# BMS_Design_2_New_Part_Monitor.net
KiCad netlist of a schematic drawn in Altium Designer
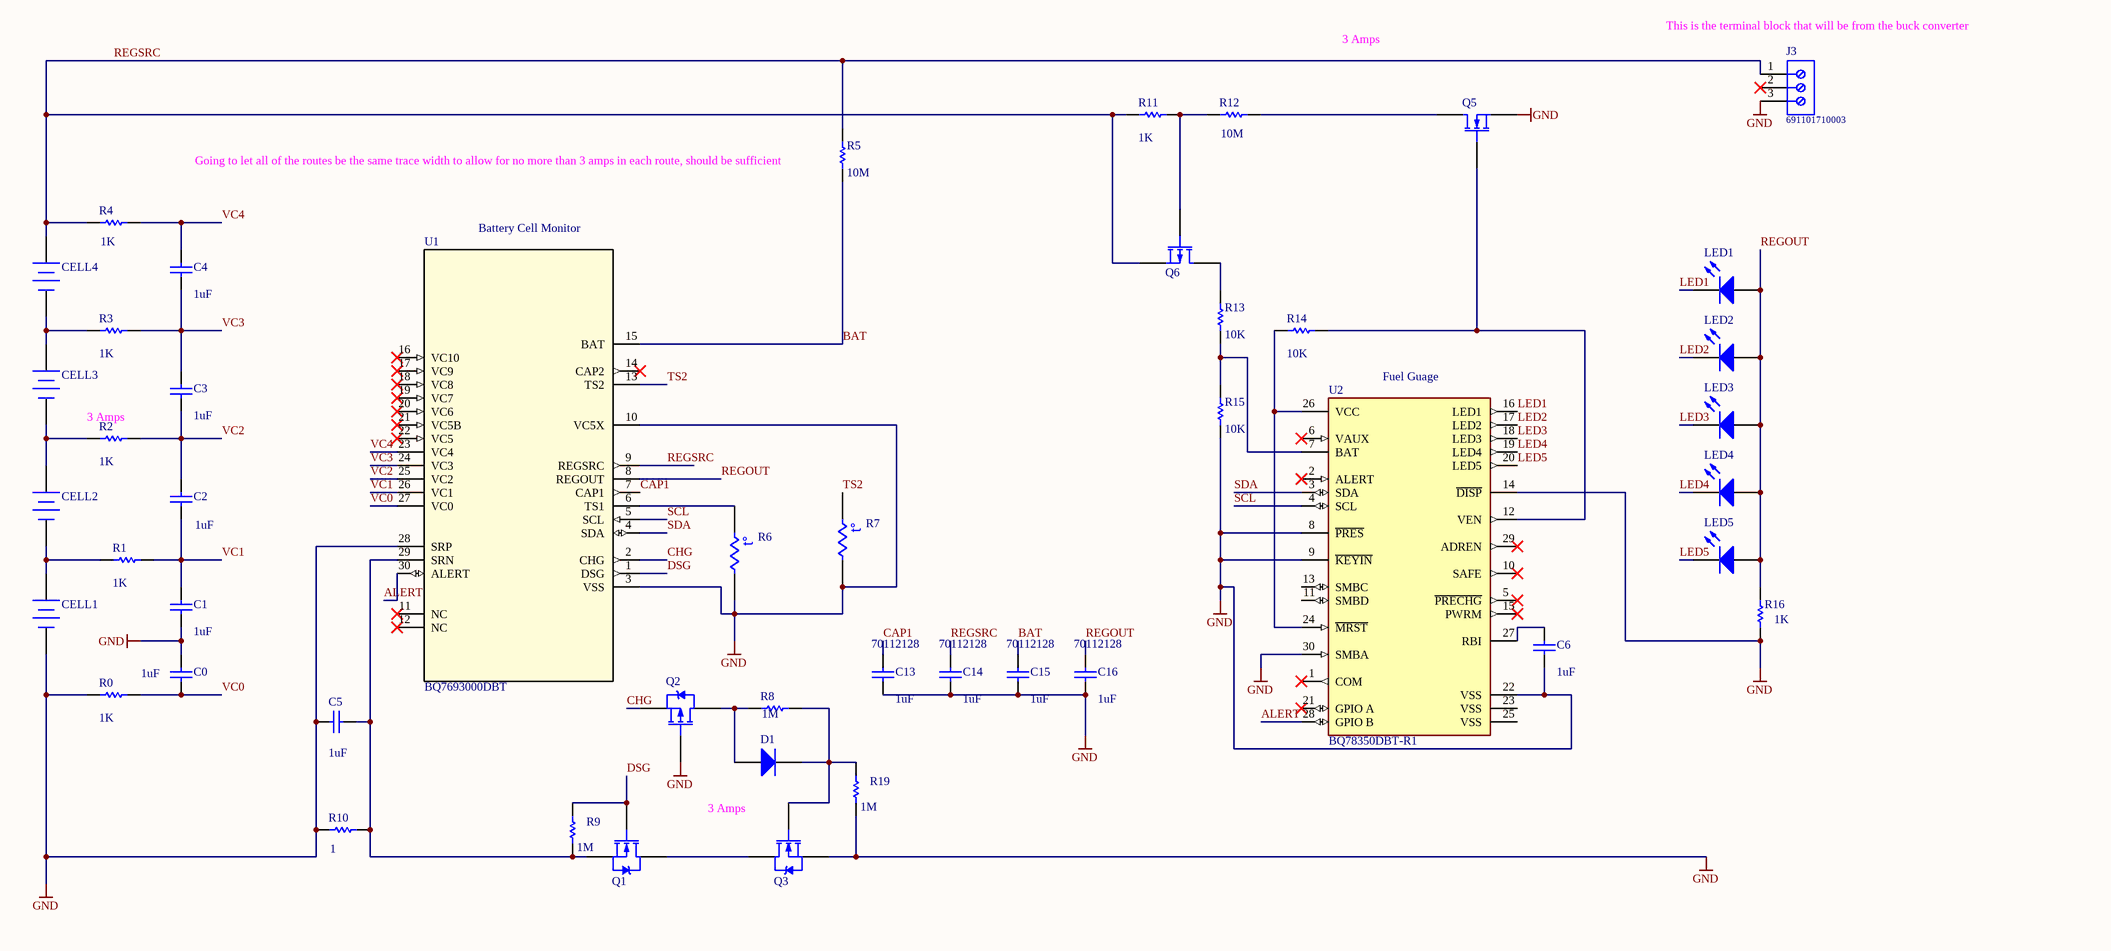
[diagram p0: BMS Design 2 New Part Monitor.SchDoc]

(export (version "E")
  (design (tool "Eeschema 10.0.6"))
  (components
    (comp (ref "C0")
      (value "1uF")
      (footprint "RAD-0.3")
      (description "Capacitor")
      (fields (field (name "PUBLISHER") "Altium Limited"))
      (libsource (lib "Miscellaneous Devices") (part "Cap"))
    )
    (comp (ref "C1")
      (value "1uF")
      (footprint "RAD-0.3")
      (description "Capacitor")
      (fields (field (name "PUBLISHER") "Altium Limited"))
      (libsource (lib "Miscellaneous Devices") (part "Cap"))
    )
    (comp (ref "C2")
      (value "1uF")
      (footprint "RAD-0.3")
      (description "Capacitor")
      (fields (field (name "PUBLISHER") "Altium Limited"))
      (libsource (lib "Miscellaneous Devices") (part "Cap"))
    )
    (comp (ref "C3")
      (value "1uF")
      (footprint "RAD-0.3")
      (description "Capacitor")
      (fields (field (name "PUBLISHER") "Altium Limited"))
      (libsource (lib "Miscellaneous Devices") (part "Cap"))
    )
    (comp (ref "C4")
      (value "1uF")
      (footprint "RAD-0.3")
      (description "Capacitor")
      (fields (field (name "PUBLISHER") "Altium Limited"))
      (libsource (lib "Miscellaneous Devices") (part "Cap"))
    )
    (comp (ref "C5")
      (value "1uF")
      (footprint "RAD-0.3")
      (description "Capacitor")
      (fields (field (name "PUBLISHER") "Altium Limited"))
      (libsource (lib "Miscellaneous Devices") (part "Cap"))
    )
    (comp (ref "C6")
      (value "1uF")
      (footprint "RAD-0.3")
      (description "Capacitor")
      (fields (field (name "PUBLISHER") "Altium Limited"))
      (libsource (lib "Miscellaneous Devices") (part "Cap"))
    )
    (comp (ref "C13")
      (value "1uF")
      (footprint "RAD-0.3")
      (description "Capacitor")
      (fields (field (name "SUPPLIER PART NUMBER 1") "70112128") (field (name "PUBLISHER") "Altium Limited"))
      (libsource (lib "Miscellaneous Devices") (part "Cap"))
    )
    (comp (ref "C14")
      (value "1uF")
      (footprint "RAD-0.3")
      (description "Capacitor")
      (fields (field (name "SUPPLIER PART NUMBER 1") "70112128") (field (name "PUBLISHER") "Altium Limited"))
      (libsource (lib "Miscellaneous Devices") (part "Cap"))
    )
    (comp (ref "C15")
      (value "1uF")
      (footprint "RAD-0.3")
      (description "Capacitor")
      (fields (field (name "SUPPLIER PART NUMBER 1") "70112128") (field (name "PUBLISHER") "Altium Limited"))
      (libsource (lib "Miscellaneous Devices") (part "Cap"))
    )
    (comp (ref "C16")
      (value "1uF")
      (footprint "RAD-0.3")
      (description "Capacitor")
      (fields (field (name "SUPPLIER PART NUMBER 1") "70112128") (field (name "PUBLISHER") "Altium Limited"))
      (libsource (lib "Miscellaneous Devices") (part "Cap"))
    )
    (comp (ref "CELL1")
      (value "~")
      (footprint "BAT-2")
      (description "Multicell Battery")
      (fields (field (name "PUBLISHER") "Altium Limited"))
      (libsource (lib "Miscellaneous Devices") (part "Battery"))
    )
    (comp (ref "CELL2")
      (value "~")
      (footprint "BAT-2")
      (description "Multicell Battery")
      (fields (field (name "PUBLISHER") "Altium Limited"))
      (libsource (lib "Miscellaneous Devices") (part "Battery"))
    )
    (comp (ref "CELL3")
      (value "~")
      (footprint "BAT-2")
      (description "Multicell Battery")
      (fields (field (name "PUBLISHER") "Altium Limited"))
      (libsource (lib "Miscellaneous Devices") (part "Battery"))
    )
    (comp (ref "CELL4")
      (value "~")
      (footprint "BAT-2")
      (description "Multicell Battery")
      (fields (field (name "PUBLISHER") "Altium Limited"))
      (libsource (lib "Miscellaneous Devices") (part "Battery"))
    )
    (comp (ref "D1")
      (value "~")
      (footprint "SMC")
      (description "Default Diode")
      (fields (field (name "PUBLISHER") "Altium Limited"))
      (libsource (lib "Miscellaneous Devices") (part "Diode"))
    )
    (comp (ref "J3")
      (value "691101710003")
      (footprint "691101710003")
      (description "Series 101 - 5.00 mm Horizontal Entry Modular with Pressure Clamp WR-TBL, 3 pin")
      (fields (field (name "MANUFACTURER") "Wurth Elektronik") (field (name "PUBLISHER") "WurthElektronik"))
      (libsource (lib "Altium Content Vault") (part "WE-CN-1P-F-TB3"))
    )
    (comp (ref "LED1")
      (value "~")
      (footprint "LED-0")
      (description "Typical INFRARED GaAs LED")
      (fields (field (name "PUBLISHER") "Altium Limited"))
      (libsource (lib "Miscellaneous Devices") (part "LED0"))
    )
    (comp (ref "LED2")
      (value "~")
      (footprint "LED-0")
      (description "Typical INFRARED GaAs LED")
      (fields (field (name "PUBLISHER") "Altium Limited"))
      (libsource (lib "Miscellaneous Devices") (part "LED0"))
    )
    (comp (ref "LED3")
      (value "~")
      (footprint "LED-0")
      (description "Typical INFRARED GaAs LED")
      (fields (field (name "PUBLISHER") "Altium Limited"))
      (libsource (lib "Miscellaneous Devices") (part "LED0"))
    )
    (comp (ref "LED4")
      (value "~")
      (footprint "LED-0")
      (description "Typical INFRARED GaAs LED")
      (fields (field (name "PUBLISHER") "Altium Limited"))
      (libsource (lib "Miscellaneous Devices") (part "LED0"))
    )
    (comp (ref "LED5")
      (value "~")
      (footprint "LED-0")
      (description "Typical INFRARED GaAs LED")
      (fields (field (name "PUBLISHER") "Altium Limited"))
      (libsource (lib "Miscellaneous Devices") (part "LED0"))
    )
    (comp (ref "Q1")
      (value "~")
      (footprint "TO-220AB")
      (description "N-Channel Power MOSFET")
      (fields (field (name "PUBLISHER") "Altium Limited"))
      (libsource (lib "Miscellaneous Devices") (part "NMOS-2"))
    )
    (comp (ref "Q2")
      (value "~")
      (footprint "TO-220AB")
      (description "P-Channel Power MOSFET")
      (fields (field (name "PUBLISHER") "Altium Limited"))
      (libsource (lib "Miscellaneous Devices") (part "PMOS-2"))
    )
    (comp (ref "Q3")
      (value "~")
      (footprint "TO-220AB")
      (description "N-Channel Power MOSFET")
      (fields (field (name "PUBLISHER") "Altium Limited"))
      (libsource (lib "Miscellaneous Devices") (part "NMOS-2"))
    )
    (comp (ref "Q5")
      (value "~")
      (footprint "E3")
      (description "N-Channel MOSFET")
      (fields (field (name "PUBLISHER") "Altium Limited"))
      (libsource (lib "Miscellaneous Devices") (part "MOSFET-N"))
    )
    (comp (ref "Q6")
      (value "~")
      (footprint "E3")
      (description "P-Channel MOSFET")
      (fields (field (name "PUBLISHER") "Altium Limited"))
      (libsource (lib "Miscellaneous Devices") (part "MOSFET-P"))
    )
    (comp (ref "R0")
      (value "1K")
      (footprint "AXIAL-0.3")
      (description "Resistor")
      (fields (field (name "PUBLISHER") "Altium Limited"))
      (libsource (lib "Miscellaneous Devices") (part "Res1"))
    )
    (comp (ref "R1")
      (value "1K")
      (footprint "AXIAL-0.3")
      (description "Resistor")
      (fields (field (name "PUBLISHER") "Altium Limited"))
      (libsource (lib "Miscellaneous Devices") (part "Res1"))
    )
    (comp (ref "R2")
      (value "1K")
      (footprint "AXIAL-0.3")
      (description "Resistor")
      (fields (field (name "PUBLISHER") "Altium Limited"))
      (libsource (lib "Miscellaneous Devices") (part "Res1"))
    )
    (comp (ref "R3")
      (value "1K")
      (footprint "AXIAL-0.3")
      (description "Resistor")
      (fields (field (name "PUBLISHER") "Altium Limited"))
      (libsource (lib "Miscellaneous Devices") (part "Res1"))
    )
    (comp (ref "R4")
      (value "1K")
      (footprint "AXIAL-0.3")
      (description "Resistor")
      (fields (field (name "PUBLISHER") "Altium Limited"))
      (libsource (lib "Miscellaneous Devices") (part "Res1"))
    )
    (comp (ref "R5")
      (value "10M")
      (footprint "AXIAL-0.3")
      (description "Resistor")
      (fields (field (name "PUBLISHER") "Altium Limited"))
      (libsource (lib "Miscellaneous Devices") (part "Res1"))
    )
    (comp (ref "R6")
      (value "~")
      (footprint "6-0805_N")
      (description "Thermistor")
      (fields (field (name "PUBLISHER") "Altium Limited"))
      (libsource (lib "Miscellaneous Devices") (part "Res Thermal"))
    )
    (comp (ref "R7")
      (value "~")
      (footprint "6-0805_N")
      (description "Thermistor")
      (fields (field (name "PUBLISHER") "Altium Limited"))
      (libsource (lib "Miscellaneous Devices") (part "Res Thermal"))
    )
    (comp (ref "R8")
      (value "1M")
      (footprint "AXIAL-0.3")
      (description "Resistor")
      (fields (field (name "PUBLISHER") "Altium Limited"))
      (libsource (lib "Miscellaneous Devices") (part "Res1"))
    )
    (comp (ref "R9")
      (value "1M")
      (footprint "AXIAL-0.3")
      (description "Resistor")
      (fields (field (name "PUBLISHER") "Altium Limited"))
      (libsource (lib "Miscellaneous Devices") (part "Res1"))
    )
    (comp (ref "R10")
      (value "~")
      (footprint "AXIAL-0.3")
      (description "Resistor")
      (fields (field (name "R10") "1") (field (name "PUBLISHER") "Altium Limited"))
      (libsource (lib "Miscellaneous Devices") (part "Res1"))
    )
    (comp (ref "R11")
      (value "1K")
      (footprint "AXIAL-0.3")
      (description "Resistor")
      (fields (field (name "PUBLISHER") "Altium Limited"))
      (libsource (lib "Miscellaneous Devices") (part "Res1"))
    )
    (comp (ref "R12")
      (value "10M")
      (footprint "AXIAL-0.3")
      (description "Resistor")
      (fields (field (name "PUBLISHER") "Altium Limited"))
      (libsource (lib "Miscellaneous Devices") (part "Res1"))
    )
    (comp (ref "R13")
      (value "10K")
      (footprint "AXIAL-0.3")
      (description "Resistor")
      (fields (field (name "PUBLISHER") "Altium Limited"))
      (libsource (lib "Miscellaneous Devices") (part "Res1"))
    )
    (comp (ref "R14")
      (value "10K")
      (footprint "AXIAL-0.3")
      (description "Resistor")
      (fields (field (name "PUBLISHER") "Altium Limited"))
      (libsource (lib "Miscellaneous Devices") (part "Res1"))
    )
    (comp (ref "R15")
      (value "10K")
      (footprint "AXIAL-0.3")
      (description "Resistor")
      (fields (field (name "PUBLISHER") "Altium Limited"))
      (libsource (lib "Miscellaneous Devices") (part "Res1"))
    )
    (comp (ref "R16")
      (value "1K")
      (footprint "AXIAL-0.3")
      (description "Resistor")
      (fields (field (name "PUBLISHER") "Altium Limited"))
      (libsource (lib "Miscellaneous Devices") (part "Res1"))
    )
    (comp (ref "R19")
      (value "1M")
      (footprint "AXIAL-0.3")
      (description "Resistor")
      (fields (field (name "PUBLISHER") "Altium Limited"))
      (libsource (lib "Miscellaneous Devices") (part "Res1"))
    )
    (comp (ref "U1")
      (value "BQ7693000DBT")
      (footprint "BQ7693000DBT:DBT0030A_N")
      (description "No Description Available")
      (fields (field (name "COPYRIGHT") "Copyright (C) 2022 Ultra Librarian. All rights reserved."))
      (libsource (lib "BQ7693000DBT") (part "BQ7693000DBT"))
    )
    (comp (ref "U2")
      (value "BQ78350DBT-R1")
      (footprint "FP-DBT0030A-IPC_C")
      (description "IC BATTERY MGMT CTRLR 30TSSOP")
      (libsource (lib "Altium Content Vault") (part "ce2f43281ae33b5194046e95201acc2"))
    )
  )
  (nets
    (net (code "1") (name "/ALERT") (class "Default")
      (node (ref "U1") (pin "30") (pinfunction "ALERT_30") (pintype "bidirectional"))
      (node (ref "U2") (pin "28") (pinfunction "GPIO_B_28") (pintype "bidirectional"))
    )
    (net (code "2") (name "/BAT") (class "Default")
      (node (ref "C15") (pin "2") (pinfunction "2_2") (pintype "passive"))
      (node (ref "R5") (pin "1") (pinfunction "1_1") (pintype "passive"))
      (node (ref "U1") (pin "15") (pinfunction "BAT_15") (pintype "power_in"))
    )
    (net (code "3") (name "/CAP1") (class "Default")
      (node (ref "C13") (pin "2") (pinfunction "2_2") (pintype "passive"))
      (node (ref "U1") (pin "7") (pinfunction "CAP1_7") (pintype "output"))
    )
    (net (code "4") (name "/CHG") (class "Default")
      (node (ref "Q2") (pin "3") (pinfunction "S_3") (pintype "passive"))
      (node (ref "U1") (pin "2") (pinfunction "CHG_2") (pintype "output"))
    )
    (net (code "5") (name "/DSG") (class "Default")
      (node (ref "Q1") (pin "1") (pinfunction "G_1") (pintype "passive"))
      (node (ref "R9") (pin "2") (pinfunction "2_2") (pintype "passive"))
      (node (ref "U1") (pin "1") (pinfunction "DSG_1") (pintype "output"))
    )
    (net (code "6") (name "/LED1") (class "Default")
      (node (ref "LED1") (pin "2") (pinfunction "K_2") (pintype "passive"))
      (node (ref "U2") (pin "16") (pinfunction "LED1_16") (pintype "output"))
    )
    (net (code "7") (name "/LED2") (class "Default")
      (node (ref "LED2") (pin "2") (pinfunction "K_2") (pintype "passive"))
      (node (ref "U2") (pin "17") (pinfunction "LED2_17") (pintype "output"))
    )
    (net (code "8") (name "/LED3") (class "Default")
      (node (ref "LED3") (pin "2") (pinfunction "K_2") (pintype "passive"))
      (node (ref "U2") (pin "18") (pinfunction "LED3_18") (pintype "output"))
    )
    (net (code "9") (name "/LED4") (class "Default")
      (node (ref "LED4") (pin "2") (pinfunction "K_2") (pintype "passive"))
      (node (ref "U2") (pin "19") (pinfunction "LED4_19") (pintype "output"))
    )
    (net (code "10") (name "/LED5") (class "Default")
      (node (ref "LED5") (pin "2") (pinfunction "K_2") (pintype "passive"))
      (node (ref "U2") (pin "20") (pinfunction "LED5_20") (pintype "output"))
    )
    (net (code "11") (name "/REGOUT") (class "Default")
      (node (ref "C16") (pin "2") (pinfunction "2_2") (pintype "passive"))
      (node (ref "LED1") (pin "1") (pinfunction "A_1") (pintype "passive"))
      (node (ref "LED2") (pin "1") (pinfunction "A_1") (pintype "passive"))
      (node (ref "LED3") (pin "1") (pinfunction "A_1") (pintype "passive"))
      (node (ref "LED4") (pin "1") (pinfunction "A_1") (pintype "passive"))
      (node (ref "LED5") (pin "1") (pinfunction "A_1") (pintype "passive"))
      (node (ref "R16") (pin "2") (pinfunction "2_2") (pintype "passive"))
      (node (ref "U1") (pin "8") (pinfunction "REGOUT_8") (pintype "power_in"))
    )
    (net (code "12") (name "/REGSRC") (class "Default")
      (node (ref "C14") (pin "2") (pinfunction "2_2") (pintype "passive"))
      (node (ref "CELL4") (pin "1") (pinfunction "+_1") (pintype "passive"))
      (node (ref "J3") (pin "1") (pinfunction "1_1") (pintype "passive"))
      (node (ref "Q6") (pin "3") (pinfunction "S_3") (pintype "passive"))
      (node (ref "R11") (pin "1") (pinfunction "1_1") (pintype "passive"))
      (node (ref "R4") (pin "1") (pinfunction "1_1") (pintype "passive"))
      (node (ref "R5") (pin "2") (pinfunction "2_2") (pintype "passive"))
      (node (ref "U1") (pin "9") (pinfunction "REGSRC_9") (pintype "output"))
    )
    (net (code "13") (name "/SCL") (class "Default")
      (node (ref "U1") (pin "5") (pinfunction "SCL_5") (pintype "input"))
      (node (ref "U2") (pin "4") (pinfunction "SCL_4") (pintype "bidirectional"))
    )
    (net (code "14") (name "/SDA") (class "Default")
      (node (ref "U1") (pin "4") (pinfunction "SDA_4") (pintype "bidirectional"))
      (node (ref "U2") (pin "3") (pinfunction "SDA_3") (pintype "bidirectional"))
    )
    (net (code "15") (name "/TS2") (class "Default")
      (node (ref "R7") (pin "1") (pinfunction "1_1") (pintype "passive"))
      (node (ref "U1") (pin "13") (pinfunction "TS2_13") (pintype "passive"))
    )
    (net (code "16") (name "/VC0") (class "Default")
      (node (ref "C0") (pin "1") (pinfunction "1_1") (pintype "passive"))
      (node (ref "R0") (pin "2") (pinfunction "2_2") (pintype "passive"))
      (node (ref "U1") (pin "27") (pinfunction "VC0_27") (pintype "passive"))
    )
    (net (code "17") (name "/VC1") (class "Default")
      (node (ref "C1") (pin "2") (pinfunction "2_2") (pintype "passive"))
      (node (ref "C2") (pin "1") (pinfunction "1_1") (pintype "passive"))
      (node (ref "R1") (pin "2") (pinfunction "2_2") (pintype "passive"))
      (node (ref "U1") (pin "26") (pinfunction "VC1_26") (pintype "passive"))
    )
    (net (code "18") (name "/VC2") (class "Default")
      (node (ref "C2") (pin "2") (pinfunction "2_2") (pintype "passive"))
      (node (ref "C3") (pin "1") (pinfunction "1_1") (pintype "passive"))
      (node (ref "R2") (pin "2") (pinfunction "2_2") (pintype "passive"))
      (node (ref "U1") (pin "25") (pinfunction "VC2_25") (pintype "passive"))
    )
    (net (code "19") (name "/VC3") (class "Default")
      (node (ref "C3") (pin "2") (pinfunction "2_2") (pintype "passive"))
      (node (ref "C4") (pin "1") (pinfunction "1_1") (pintype "passive"))
      (node (ref "R3") (pin "2") (pinfunction "2_2") (pintype "passive"))
      (node (ref "U1") (pin "24") (pinfunction "VC3_24") (pintype "passive"))
    )
    (net (code "20") (name "/VC4") (class "Default")
      (node (ref "C4") (pin "2") (pinfunction "2_2") (pintype "passive"))
      (node (ref "R4") (pin "2") (pinfunction "2_2") (pintype "passive"))
      (node (ref "U1") (pin "23") (pinfunction "VC4_23") (pintype "passive"))
    )
    (net (code "21") (name "GND") (class "Default")
      (node (ref "C0") (pin "2") (pinfunction "2_2") (pintype "passive"))
      (node (ref "C1") (pin "1") (pinfunction "1_1") (pintype "passive"))
      (node (ref "C13") (pin "1") (pinfunction "1_1") (pintype "passive"))
      (node (ref "C14") (pin "1") (pinfunction "1_1") (pintype "passive"))
      (node (ref "C15") (pin "1") (pinfunction "1_1") (pintype "passive"))
      (node (ref "C16") (pin "1") (pinfunction "1_1") (pintype "passive"))
      (node (ref "C5") (pin "1") (pinfunction "1_1") (pintype "passive"))
      (node (ref "C6") (pin "1") (pinfunction "1_1") (pintype "passive"))
      (node (ref "CELL1") (pin "2") (pinfunction "-_2") (pintype "passive"))
      (node (ref "J3") (pin "3") (pinfunction "3_3") (pintype "passive"))
      (node (ref "Q2") (pin "1") (pinfunction "G_1") (pintype "passive"))
      (node (ref "Q3") (pin "3") (pinfunction "S_3") (pintype "passive"))
      (node (ref "Q5") (pin "3") (pinfunction "S_3") (pintype "passive"))
      (node (ref "R0") (pin "1") (pinfunction "1_1") (pintype "passive"))
      (node (ref "R10") (pin "1") (pinfunction "1_1") (pintype "passive"))
      (node (ref "R15") (pin "1") (pinfunction "1_1") (pintype "passive"))
      (node (ref "R16") (pin "1") (pinfunction "1_1") (pintype "passive"))
      (node (ref "R19") (pin "1") (pinfunction "1_1") (pintype "passive"))
      (node (ref "R6") (pin "2") (pinfunction "2_2") (pintype "passive"))
      (node (ref "R7") (pin "2") (pinfunction "2_2") (pintype "passive"))
      (node (ref "U1") (pin "10") (pinfunction "VC5X_10") (pintype "passive"))
      (node (ref "U1") (pin "28") (pinfunction "SRP_28") (pintype "passive"))
      (node (ref "U1") (pin "3") (pinfunction "VSS_3") (pintype "power_in"))
      (node (ref "U2") (pin "14") (pinfunction "~{DISP}_14") (pintype "passive"))
      (node (ref "U2") (pin "22") (pinfunction "VSS_22") (pintype "passive"))
      (node (ref "U2") (pin "30") (pinfunction "SMBA_30") (pintype "input"))
      (node (ref "U2") (pin "8") (pinfunction "~{PRES}_8") (pintype "passive"))
      (node (ref "U2") (pin "9") (pinfunction "~{KEYIN}_9") (pintype "passive"))
    )
    (net (code "22") (name "Net-(CELL1-+)") (class "Default")
      (node (ref "CELL1") (pin "1") (pinfunction "+_1") (pintype "passive"))
      (node (ref "CELL2") (pin "2") (pinfunction "-_2") (pintype "passive"))
      (node (ref "R1") (pin "1") (pinfunction "1_1") (pintype "passive"))
    )
    (net (code "23") (name "Net-(CELL2-+)") (class "Default")
      (node (ref "CELL2") (pin "1") (pinfunction "+_1") (pintype "passive"))
      (node (ref "CELL3") (pin "2") (pinfunction "-_2") (pintype "passive"))
      (node (ref "R2") (pin "1") (pinfunction "1_1") (pintype "passive"))
    )
    (net (code "24") (name "Net-(CELL3-+)") (class "Default")
      (node (ref "CELL3") (pin "1") (pinfunction "+_1") (pintype "passive"))
      (node (ref "CELL4") (pin "2") (pinfunction "-_2") (pintype "passive"))
      (node (ref "R3") (pin "1") (pinfunction "1_1") (pintype "passive"))
    )
    (net (code "25") (name "Net-(D1-A)") (class "Default")
      (node (ref "D1") (pin "1") (pinfunction "A_1") (pintype "passive"))
      (node (ref "Q2") (pin "2") (pinfunction "D_2") (pintype "passive"))
      (node (ref "R8") (pin "2") (pinfunction "2_2") (pintype "passive"))
    )
    (net (code "26") (name "Net-(D1-K)") (class "Default")
      (node (ref "D1") (pin "2") (pinfunction "K_2") (pintype "passive"))
      (node (ref "Q3") (pin "1") (pinfunction "G_1") (pintype "passive"))
      (node (ref "R19") (pin "2") (pinfunction "2_2") (pintype "passive"))
      (node (ref "R8") (pin "1") (pinfunction "1_1") (pintype "passive"))
    )
    (net (code "27") (name "Net-(Q1-D)") (class "Default")
      (node (ref "Q1") (pin "2") (pinfunction "D_2") (pintype "passive"))
      (node (ref "Q3") (pin "2") (pinfunction "D_2") (pintype "passive"))
    )
    (net (code "28") (name "Net-(Q1-S)") (class "Default")
      (node (ref "C5") (pin "2") (pinfunction "2_2") (pintype "passive"))
      (node (ref "Q1") (pin "3") (pinfunction "S_3") (pintype "passive"))
      (node (ref "R10") (pin "2") (pinfunction "2_2") (pintype "passive"))
      (node (ref "R9") (pin "1") (pinfunction "1_1") (pintype "passive"))
      (node (ref "U1") (pin "29") (pinfunction "SRN_29") (pintype "passive"))
    )
    (net (code "29") (name "Net-(Q5-D)") (class "Default")
      (node (ref "Q5") (pin "1") (pinfunction "D_1") (pintype "passive"))
      (node (ref "R12") (pin "2") (pinfunction "2_2") (pintype "passive"))
    )
    (net (code "30") (name "Net-(Q5-G)") (class "Default")
      (node (ref "Q5") (pin "2") (pinfunction "G_2") (pintype "passive"))
      (node (ref "R14") (pin "2") (pinfunction "2_2") (pintype "passive"))
      (node (ref "U2") (pin "12") (pinfunction "VEN_12") (pintype "output"))
    )
    (net (code "31") (name "Net-(Q6-D)") (class "Default")
      (node (ref "Q6") (pin "1") (pinfunction "D_1") (pintype "passive"))
      (node (ref "R13") (pin "2") (pinfunction "2_2") (pintype "passive"))
    )
    (net (code "32") (name "Net-(Q6-G)") (class "Default")
      (node (ref "Q6") (pin "2") (pinfunction "G_2") (pintype "passive"))
      (node (ref "R11") (pin "2") (pinfunction "2_2") (pintype "passive"))
      (node (ref "R12") (pin "1") (pinfunction "1_1") (pintype "passive"))
    )
    (net (code "33") (name "Net-(U1-TS1)") (class "Default")
      (node (ref "R6") (pin "1") (pinfunction "1_1") (pintype "passive"))
      (node (ref "U1") (pin "6") (pinfunction "TS1_6") (pintype "passive"))
    )
    (net (code "34") (name "Net-(U2-BAT)") (class "Default")
      (node (ref "R13") (pin "1") (pinfunction "1_1") (pintype "passive"))
      (node (ref "R15") (pin "2") (pinfunction "2_2") (pintype "passive"))
      (node (ref "U2") (pin "7") (pinfunction "BAT_7") (pintype "passive"))
    )
    (net (code "35") (name "Net-(U2-RBI)") (class "Default")
      (node (ref "C6") (pin "2") (pinfunction "2_2") (pintype "passive"))
      (node (ref "U2") (pin "27") (pinfunction "RBI_27") (pintype "power_in"))
    )
    (net (code "36") (name "Net-(U2-VCC)") (class "Default")
      (node (ref "R14") (pin "1") (pinfunction "1_1") (pintype "passive"))
      (node (ref "U2") (pin "24") (pinfunction "~{MRST}_24") (pintype "input"))
      (node (ref "U2") (pin "26") (pinfunction "VCC_26") (pintype "power_in"))
    )
    (net (code "37") (name "unconnected-(J3-Pad2)") (class "Default")
      (node (ref "J3") (pin "2") (pinfunction "2_2") (pintype "passive+no_connect"))
    )
    (net (code "38") (name "unconnected-(U1-CAP2-Pad14)") (class "Default")
      (node (ref "U1") (pin "14") (pinfunction "CAP2_14") (pintype "output+no_connect"))
    )
    (net (code "39") (name "unconnected-(U1-NC-Pad11)") (class "Default")
      (node (ref "U1") (pin "11") (pinfunction "NC_11") (pintype "passive+no_connect"))
    )
    (net (code "40") (name "unconnected-(U1-NC-Pad12)") (class "Default")
      (node (ref "U1") (pin "12") (pinfunction "NC_12") (pintype "passive+no_connect"))
    )
    (net (code "41") (name "unconnected-(U1-VC5-Pad22)") (class "Default")
      (node (ref "U1") (pin "22") (pinfunction "VC5_22") (pintype "input+no_connect"))
    )
    (net (code "42") (name "unconnected-(U1-VC5B-Pad21)") (class "Default")
      (node (ref "U1") (pin "21") (pinfunction "VC5B_21") (pintype "input+no_connect"))
    )
    (net (code "43") (name "unconnected-(U1-VC6-Pad20)") (class "Default")
      (node (ref "U1") (pin "20") (pinfunction "VC6_20") (pintype "input+no_connect"))
    )
    (net (code "44") (name "unconnected-(U1-VC7-Pad19)") (class "Default")
      (node (ref "U1") (pin "19") (pinfunction "VC7_19") (pintype "input+no_connect"))
    )
    (net (code "45") (name "unconnected-(U1-VC8-Pad18)") (class "Default")
      (node (ref "U1") (pin "18") (pinfunction "VC8_18") (pintype "input+no_connect"))
    )
    (net (code "46") (name "unconnected-(U1-VC9-Pad17)") (class "Default")
      (node (ref "U1") (pin "17") (pinfunction "VC9_17") (pintype "input+no_connect"))
    )
    (net (code "47") (name "unconnected-(U1-VC10-Pad16)") (class "Default")
      (node (ref "U1") (pin "16") (pinfunction "VC10_16") (pintype "input+no_connect"))
    )
    (net (code "48") (name "unconnected-(U2-ADREN-Pad29)") (class "Default")
      (node (ref "U2") (pin "29") (pinfunction "ADREN_29") (pintype "output+no_connect"))
    )
    (net (code "49") (name "unconnected-(U2-ALERT-Pad2)") (class "Default")
      (node (ref "U2") (pin "2") (pinfunction "ALERT_2") (pintype "input+no_connect"))
    )
    (net (code "50") (name "unconnected-(U2-COM-Pad1)") (class "Default")
      (node (ref "U2") (pin "1") (pinfunction "COM_1") (pintype "output+no_connect"))
    )
    (net (code "51") (name "unconnected-(U2-GPIO_A-Pad21)") (class "Default")
      (node (ref "U2") (pin "21") (pinfunction "GPIO_A_21") (pintype "bidirectional+no_connect"))
    )
    (net (code "52") (name "unconnected-(U2-PWRM-Pad15)") (class "Default")
      (node (ref "U2") (pin "15") (pinfunction "PWRM_15") (pintype "output+no_connect"))
    )
    (net (code "53") (name "unconnected-(U2-SAFE-Pad10)") (class "Default")
      (node (ref "U2") (pin "10") (pinfunction "SAFE_10") (pintype "output+no_connect"))
    )
    (net (code "54") (name "unconnected-(U2-SMBC-Pad13)") (class "Default")
      (node (ref "U2") (pin "13") (pinfunction "SMBC_13") (pintype "bidirectional"))
    )
    (net (code "55") (name "unconnected-(U2-SMBD-Pad11)") (class "Default")
      (node (ref "U2") (pin "11") (pinfunction "SMBD_11") (pintype "bidirectional"))
    )
    (net (code "56") (name "unconnected-(U2-VAUX-Pad6)") (class "Default")
      (node (ref "U2") (pin "6") (pinfunction "VAUX_6") (pintype "input+no_connect"))
    )
    (net (code "57") (name "unconnected-(U2-VSS-Pad23)") (class "Default")
      (node (ref "U2") (pin "23") (pinfunction "VSS_23") (pintype "power_in"))
    )
    (net (code "58") (name "unconnected-(U2-VSS-Pad25)") (class "Default")
      (node (ref "U2") (pin "25") (pinfunction "VSS_25") (pintype "power_in"))
    )
    (net (code "59") (name "unconnected-(U2-~{PRECHG}-Pad5)") (class "Default")
      (node (ref "U2") (pin "5") (pinfunction "~{PRECHG}_5") (pintype "output+no_connect"))
    )
  )
)
